# Antenna_and_LoRa.net
KiCad netlist of a schematic drawn in Altium Designer
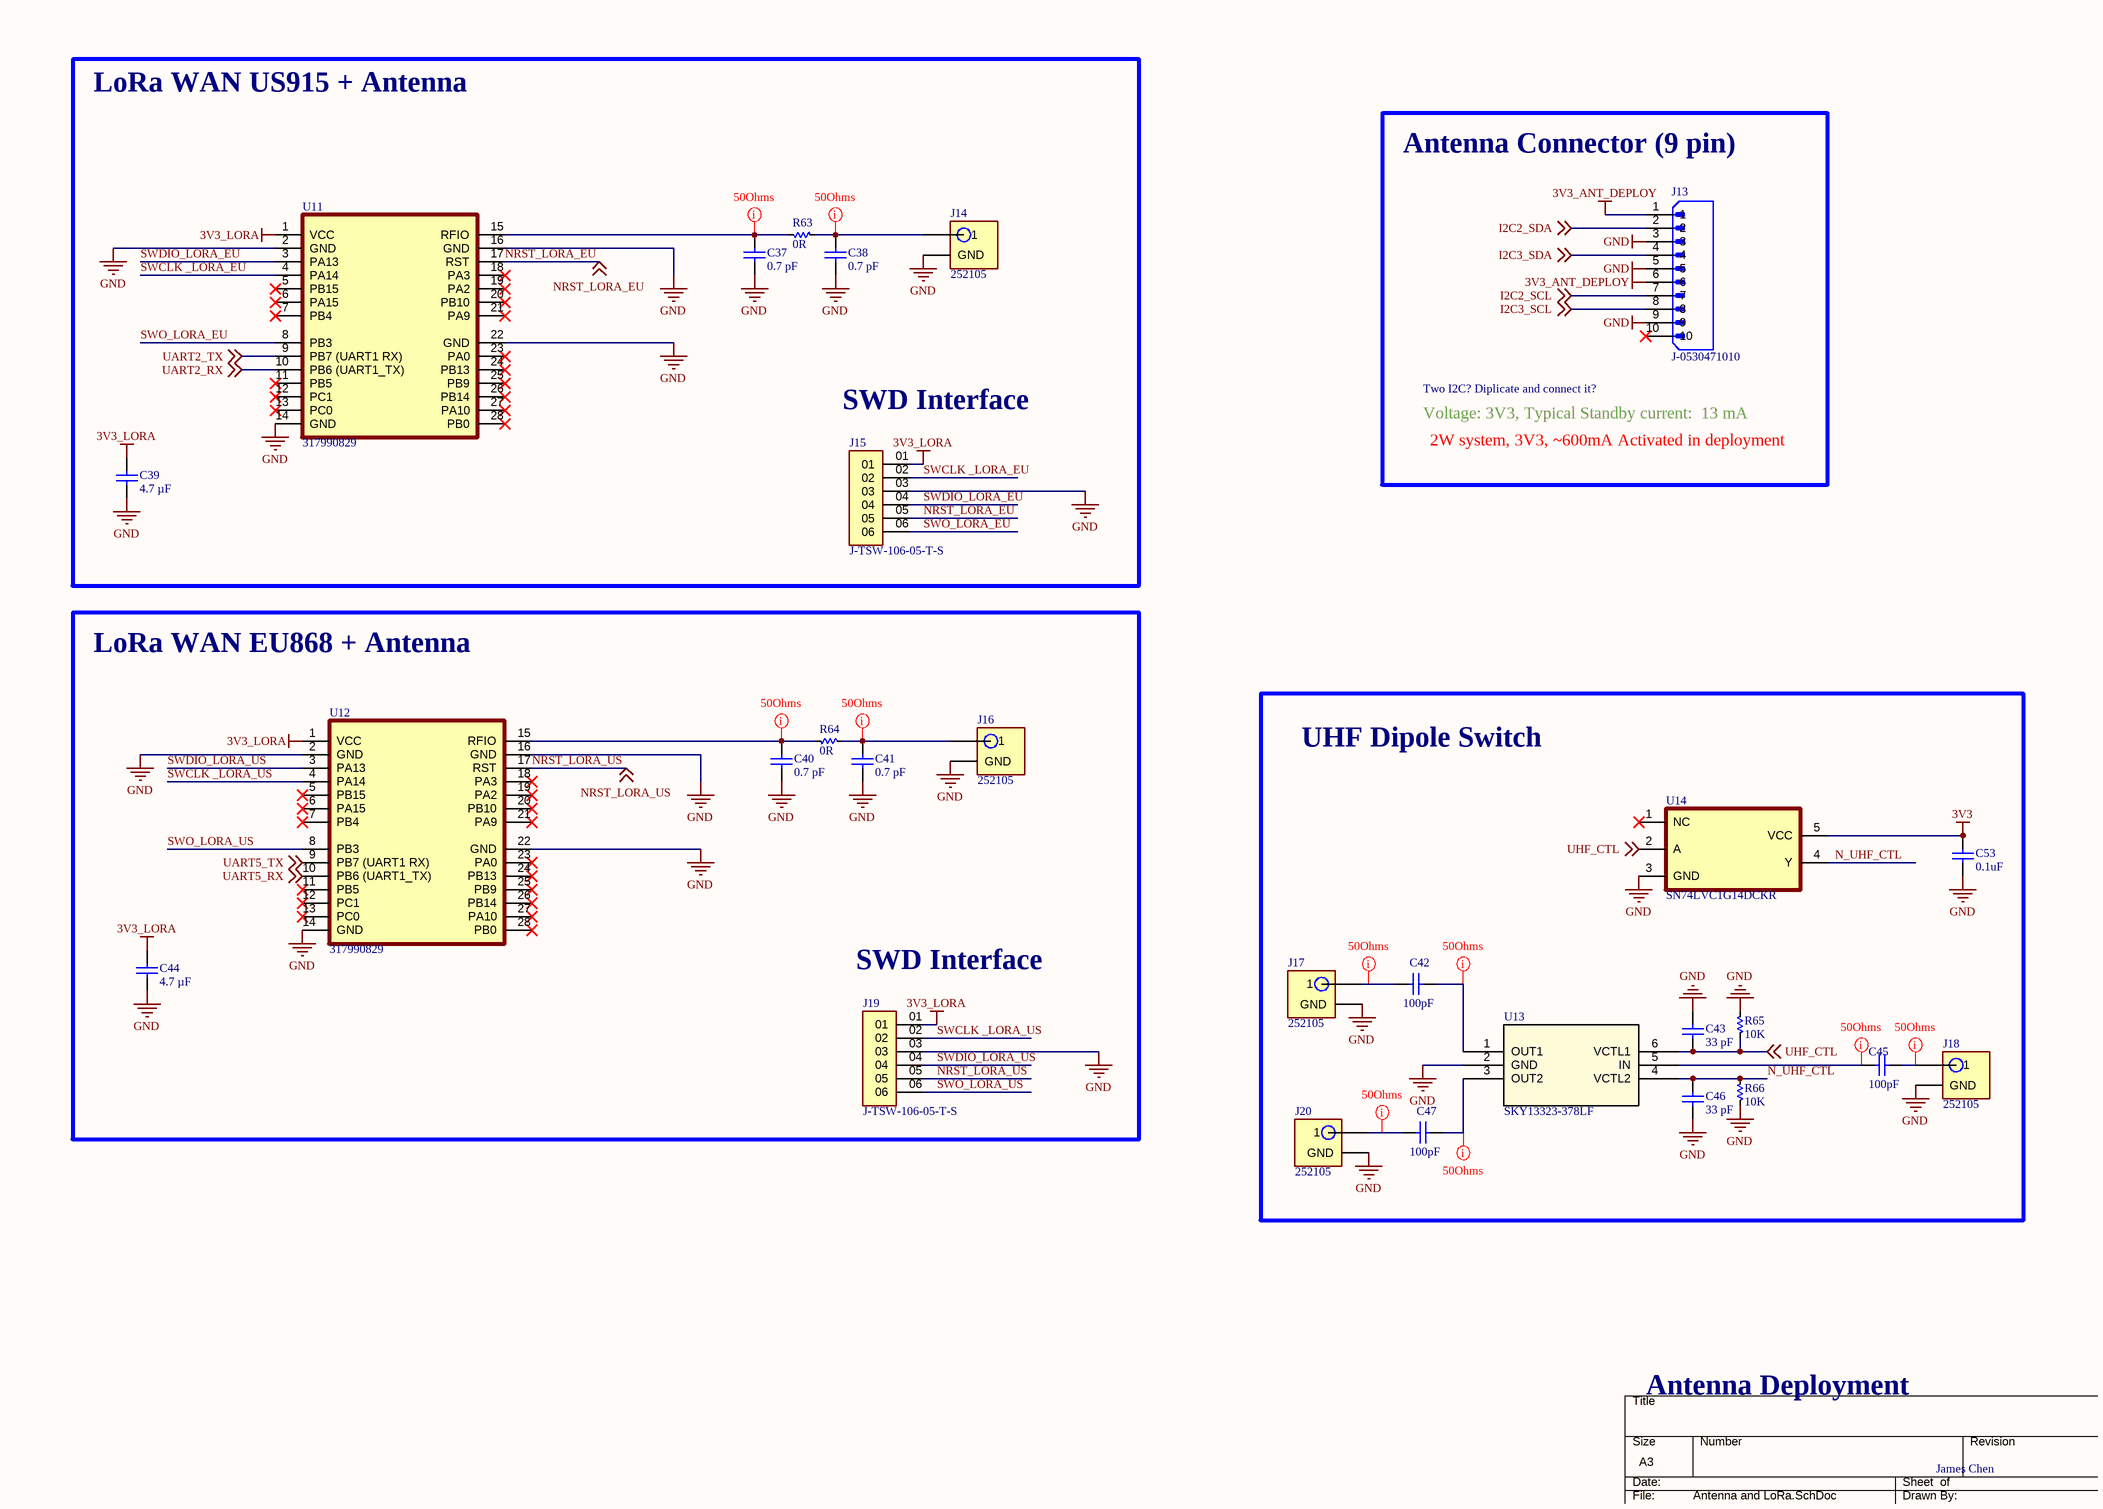
[diagram p0: Antenna and LoRa.SchDoc]

(export (version "E")
  (design (tool "Eeschema 10.0.6"))
  (components
    (comp (ref "C37")
      (value "0.7 pF")
      (footprint "0603")
      (description "CAP CER 0.7PF 50V NP0 0603")
      (fields
        (field (name "DISTRIBUTOR PART #") "399-CBR06C708B5GACCT-ND")
        (field (name "MANUFACTURER") "KEMET")
      )
      (libsource (lib "UHF Radio rev1.0") (part "CC-710-K-50V-X7R-0603"))
    )
    (comp (ref "C38")
      (value "0.7 pF")
      (footprint "0603")
      (description "CAP CER 0.7PF 50V NP0 0603")
      (fields
        (field (name "DISTRIBUTOR PART #") "399-CBR06C708B5GACCT-ND")
        (field (name "MANUFACTURER") "KEMET")
      )
      (libsource (lib "UHF Radio rev1.0") (part "CC-710-K-50V-X7R-0603"))
    )
    (comp (ref "C39")
      (value "4.7 µF")
      (footprint "0603")
      (description "CAP CER 4.7UF 16V X7R 0603")
      (fields
        (field (name "DISTRIBUTOR PART #") "490-GRM188Z71C475KE21JCT-ND")
        (field (name "MANUFACTURER") "Murata Electronics")
      )
      (libsource (lib "RS2D") (part "CC-475-K-16V-X7R-0603"))
    )
    (comp (ref "C40")
      (value "0.7 pF")
      (footprint "0603")
      (description "CAP CER 0.7PF 50V NP0 0603")
      (fields
        (field (name "DISTRIBUTOR PART #") "399-CBR06C708B5GACCT-ND")
        (field (name "MANUFACTURER") "KEMET")
      )
      (libsource (lib "UHF Radio rev1.0") (part "CC-710-K-50V-X7R-0603"))
    )
    (comp (ref "C41")
      (value "0.7 pF")
      (footprint "0603")
      (description "CAP CER 0.7PF 50V NP0 0603")
      (fields
        (field (name "DISTRIBUTOR PART #") "399-CBR06C708B5GACCT-ND")
        (field (name "MANUFACTURER") "KEMET")
      )
      (libsource (lib "UHF Radio rev1.0") (part "CC-710-K-50V-X7R-0603"))
    )
    (comp (ref "C42")
      (value "100pF")
      (footprint "0603")
      (description "CAP CER 100PF 50V X7R 0603")
      (fields (field (name "DISTRIBUTOR PART #") "311-3601-1-ND") (field (name "MANUFACTURER") "YAGEO"))
      (libsource (lib "RS2D") (part "CC-108-K-50V-X7R-0603"))
    )
    (comp (ref "C43")
      (value "33 pF")
      (footprint "0603")
      (description "CAP CER 33PF 50V X7R 0603")
      (fields
        (field (name "DISTRIBUTOR PART #") "399-C0603C330K5RAC7867CT-ND")
        (field (name "MANUFACTURER") "KEMET")
      )
      (libsource (lib "OBC Development Board") (part "CC-339-K-50V-X7R-0603"))
    )
    (comp (ref "C44")
      (value "4.7 µF")
      (footprint "0603")
      (description "CAP CER 4.7UF 16V X7R 0603")
      (fields
        (field (name "DISTRIBUTOR PART #") "490-GRM188Z71C475KE21JCT-ND")
        (field (name "MANUFACTURER") "Murata Electronics")
      )
      (libsource (lib "RS2D") (part "CC-475-K-16V-X7R-0603"))
    )
    (comp (ref "C45")
      (value "100pF")
      (footprint "0603")
      (description "CAP CER 100PF 50V X7R 0603")
      (fields (field (name "DISTRIBUTOR PART #") "311-3601-1-ND") (field (name "MANUFACTURER") "YAGEO"))
      (libsource (lib "RS2D") (part "CC-108-K-50V-X7R-0603"))
    )
    (comp (ref "C46")
      (value "33 pF")
      (footprint "0603")
      (description "CAP CER 33PF 50V X7R 0603")
      (fields
        (field (name "DISTRIBUTOR PART #") "399-C0603C330K5RAC7867CT-ND")
        (field (name "MANUFACTURER") "KEMET")
      )
      (libsource (lib "OBC Development Board") (part "CC-339-K-50V-X7R-0603"))
    )
    (comp (ref "C47")
      (value "100pF")
      (footprint "0603")
      (description "CAP CER 100PF 50V X7R 0603")
      (fields (field (name "DISTRIBUTOR PART #") "311-3601-1-ND") (field (name "MANUFACTURER") "YAGEO"))
      (libsource (lib "RS2D") (part "CC-108-K-50V-X7R-0603"))
    )
    (comp (ref "C53")
      (value "0.1uF")
      (footprint "0603")
      (description "0.1 µF ±10% 25V Ceramic Capacitor X7R 0603 (1608 Metric)")
      (fields
        (field (name "DISTRIBUTOR PART #") "1276-1006-1-ND")
        (field (name "MANUFACTURER") "Samsung Electro-Mechanics")
      )
      (libsource (lib "OBC Development Board") (part "CC-104-K-25V-X7R-0603"))
    )
    (comp (ref "J13")
      (value "J-0530471010")
      (footprint "J-0530471010")
      (description "CONN HEADER VERT 10POS 1.25MM")
      (fields (field (name "MANUFACTURER") "Molex") (field (name "MANUFACTURER PART #") "0530471010"))
      (libsource (lib "OBC Development Board") (part "J-0530471010"))
    )
    (comp (ref "J14")
      (value "252105")
      (footprint "J-252105")
      (description "CONN MCX RCPT STR 50 OHM PCB")
      (fields (field (name "MANUFACTURER") "Amphenol RF") (field (name "DISTRIBUTOR PART #") "ACX1262-ND"))
      (libsource (lib "OBC Development Board") (part "J-252105"))
    )
    (comp (ref "J15")
      (value "J-TSW-106-05-T-S")
      (footprint "J-TSW-106-05-T-S")
      (description "CONN HEADER VERT 6POS 2.54MM")
      (fields
        (field (name "DISTRBUTOR PART #") "SAM12323-ND")
        (field (name "MANUFACTURER PART #") "TSW-106-05-T-S")
      )
      (libsource (lib "OBC Development Board") (part "J-TSW-106-05-T-S"))
    )
    (comp (ref "J16")
      (value "252105")
      (footprint "J-252105")
      (description "CONN MCX RCPT STR 50 OHM PCB")
      (fields (field (name "MANUFACTURER") "Amphenol RF") (field (name "DISTRIBUTOR PART #") "ACX1262-ND"))
      (libsource (lib "OBC Development Board") (part "J-252105"))
    )
    (comp (ref "J17")
      (value "252105")
      (footprint "J-252105")
      (description "CONN MCX RCPT STR 50 OHM PCB")
      (fields (field (name "MANUFACTURER") "Amphenol RF") (field (name "DISTRIBUTOR PART #") "ACX1262-ND"))
      (libsource (lib "") (part "J-252105_1"))
    )
    (comp (ref "J18")
      (value "252105")
      (footprint "J-252105")
      (description "CONN MCX RCPT STR 50 OHM PCB")
      (fields (field (name "MANUFACTURER") "Amphenol RF") (field (name "DISTRIBUTOR PART #") "ACX1262-ND"))
      (libsource (lib "OBC Development Board") (part "J-252105"))
    )
    (comp (ref "J19")
      (value "J-TSW-106-05-T-S")
      (footprint "J-TSW-106-05-T-S")
      (description "CONN HEADER VERT 6POS 2.54MM")
      (fields
        (field (name "DISTRBUTOR PART #") "SAM12323-ND")
        (field (name "MANUFACTURER PART #") "TSW-106-05-T-S")
      )
      (libsource (lib "OBC Development Board") (part "J-TSW-106-05-T-S"))
    )
    (comp (ref "J20")
      (value "252105")
      (footprint "J-252105")
      (description "CONN MCX RCPT STR 50 OHM PCB")
      (fields (field (name "MANUFACTURER") "Amphenol RF") (field (name "DISTRIBUTOR PART #") "ACX1262-ND"))
      (libsource (lib "") (part "J-252105_1"))
    )
    (comp (ref "R63")
      (value "0R")
      (footprint "0603")
      (description "0 Ohms Jumper 0.1W, 1/10W Chip Resistor 0603 (1608 Metric) Automotive AEC-Q200 Thick Film")
      (fields
        (field (name "DISTRIBUTOR PART #") "RMCF0603ZT0R00CT-ND")
        (field (name "MANUFACTURER") "Stackpole Electronics Inc")
      )
      (libsource (lib "OBC Development Board") (part "RT-0R00-F-1/10W-0603"))
    )
    (comp (ref "R64")
      (value "0R")
      (footprint "0603")
      (description "0 Ohms Jumper 0.1W, 1/10W Chip Resistor 0603 (1608 Metric) Automotive AEC-Q200 Thick Film")
      (fields
        (field (name "DISTRIBUTOR PART #") "RMCF0603ZT0R00CT-ND")
        (field (name "MANUFACTURER") "Stackpole Electronics Inc")
      )
      (libsource (lib "OBC Development Board") (part "RT-0R00-F-1/10W-0603"))
    )
    (comp (ref "R65")
      (value "10K")
      (footprint "0603")
      (description "10 kOhms ±0.1% 0.063W, 1/16W Chip Resistor 0603 (1608 Metric) - Thin Film")
      (fields
        (field (name "DISTRIBUTOR PART #") "A119886CT-ND")
        (field (name "MANUFACTURER") "TE Connectivity Passive Product")
      )
      (libsource (lib "OBC Development Board") (part "RT-10K0-F-1/16W-0603"))
    )
    (comp (ref "R66")
      (value "10K")
      (footprint "0603")
      (description "10 kOhms ±0.1% 0.063W, 1/16W Chip Resistor 0603 (1608 Metric) - Thin Film")
      (fields
        (field (name "DISTRIBUTOR PART #") "A119886CT-ND")
        (field (name "MANUFACTURER") "TE Connectivity Passive Product")
      )
      (libsource (lib "OBC Development Board") (part "RT-10K0-F-1/16W-0603"))
    )
    (comp (ref "U11")
      (value "317990829")
      (footprint "U-LORA-E5")
      (description "LORA-E5 WIRELESS MODULE (TAPE RE")
      (fields
        (field (name "MANUFACTURER") "Seeed Technology Co., Ltd")
        (field (name "DISTRIBUTOR PART #") "1597-317990829CT-ND")
      )
      (libsource (lib "OBC Development Board") (part "U-LORA-E5"))
    )
    (comp (ref "U12")
      (value "317990829")
      (footprint "U-LORA-E5")
      (description "LORA-E5 WIRELESS MODULE (TAPE RE")
      (fields
        (field (name "MANUFACTURER") "Seeed Technology Co., Ltd")
        (field (name "DISTRIBUTOR PART #") "1597-317990829CT-ND")
      )
      (libsource (lib "OBC Development Board") (part "U-LORA-E5"))
    )
    (comp (ref "U13")
      (value "SKY13323-378LF")
      (footprint "U-SKY13323-378LF")
      (description "IC RF SWITCH SPDT 3GHZ 6MLPD")
      (fields
        (field (name "MANUFACTURER") "Skyworks Solutions Inc.")
        (field (name "DISTRBUTOR PART #") "683-1334-1-ND")
      )
      (libsource (lib "OBC Development Board") (part "U-SKY13323-378LF"))
    )
    (comp (ref "U14")
      (value "SN74LVC1G14DCKR")
      (footprint "U-SN74LVC1G14DCKR")
      (description "IC INVERT SCHMITT 1CH 1IN SC70")
      (fields (field (name "DISTRIBUTOR PART NUMBER") "296-11608-1-ND"))
      (libsource (lib "OBC Development Board") (part "U-SN74LVC1G14DCKR"))
    )
  )
  (nets
    (net (code "1") (name "/N_UHF_CTL") (class "Default")
      (node (ref "C46") (pin "2") (pinfunction "2_2") (pintype "passive"))
      (node (ref "R66") (pin "2") (pintype "passive"))
      (node (ref "U13") (pin "4") (pinfunction "VCTL2_4") (pintype "passive"))
      (node (ref "U14") (pin "4") (pinfunction "Y_4") (pintype "passive"))
    )
    (net (code "2") (name "/SWCLK _LORA_EU") (class "Default")
      (node (ref "J15") (pin "02") (pinfunction "02_02") (pintype "passive"))
      (node (ref "U11") (pin "4") (pinfunction "PA14_4") (pintype "passive"))
    )
    (net (code "3") (name "/SWCLK _LORA_US") (class "Default")
      (node (ref "J19") (pin "02") (pinfunction "02_02") (pintype "passive"))
      (node (ref "U12") (pin "4") (pinfunction "PA14_4") (pintype "passive"))
    )
    (net (code "4") (name "/SWDIO_LORA_EU") (class "Default")
      (node (ref "J15") (pin "04") (pinfunction "04_04") (pintype "passive"))
      (node (ref "U11") (pin "3") (pinfunction "PA13_3") (pintype "passive"))
    )
    (net (code "5") (name "/SWDIO_LORA_US") (class "Default")
      (node (ref "J19") (pin "04") (pinfunction "04_04") (pintype "passive"))
      (node (ref "U12") (pin "3") (pinfunction "PA13_3") (pintype "passive"))
    )
    (net (code "6") (name "/SWO_LORA_EU") (class "Default")
      (node (ref "J15") (pin "06") (pinfunction "06_06") (pintype "passive"))
      (node (ref "U11") (pin "8") (pinfunction "PB3_8") (pintype "passive"))
    )
    (net (code "7") (name "/SWO_LORA_US") (class "Default")
      (node (ref "J19") (pin "06") (pinfunction "06_06") (pintype "passive"))
      (node (ref "U12") (pin "8") (pinfunction "PB3_8") (pintype "passive"))
    )
    (net (code "8") (name "3V3") (class "Default")
      (node (ref "C53") (pin "2") (pinfunction "2_2") (pintype "passive"))
      (node (ref "U14") (pin "5") (pinfunction "VCC_5") (pintype "passive"))
    )
    (net (code "9") (name "3V3_ANT_DEPLOY") (class "Default")
      (node (ref "J13") (pin "1") (pinfunction "1_1") (pintype "passive"))
      (node (ref "J13") (pin "6") (pinfunction "6_6") (pintype "passive"))
    )
    (net (code "10") (name "3V3_LORA") (class "Default")
      (node (ref "C39") (pin "2") (pinfunction "2_2") (pintype "passive"))
      (node (ref "C44") (pin "2") (pinfunction "2_2") (pintype "passive"))
      (node (ref "J15") (pin "01") (pinfunction "01_01") (pintype "passive"))
      (node (ref "J19") (pin "01") (pinfunction "01_01") (pintype "passive"))
      (node (ref "U11") (pin "1") (pinfunction "VCC_1") (pintype "passive"))
      (node (ref "U12") (pin "1") (pinfunction "VCC_1") (pintype "passive"))
    )
    (net (code "11") (name "GND") (class "Default")
      (node (ref "C37") (pin "1") (pinfunction "1_1") (pintype "passive"))
      (node (ref "C38") (pin "1") (pinfunction "1_1") (pintype "passive"))
      (node (ref "C39") (pin "1") (pinfunction "1_1") (pintype "passive"))
      (node (ref "C40") (pin "1") (pinfunction "1_1") (pintype "passive"))
      (node (ref "C41") (pin "1") (pinfunction "1_1") (pintype "passive"))
      (node (ref "C43") (pin "2") (pinfunction "2_2") (pintype "passive"))
      (node (ref "C44") (pin "1") (pinfunction "1_1") (pintype "passive"))
      (node (ref "C46") (pin "1") (pinfunction "1_1") (pintype "passive"))
      (node (ref "C53") (pin "1") (pinfunction "1_1") (pintype "passive"))
      (node (ref "J13") (pin "3") (pinfunction "3_3") (pintype "passive"))
      (node (ref "J13") (pin "5") (pinfunction "5_5") (pintype "passive"))
      (node (ref "J13") (pin "9") (pinfunction "9_9") (pintype "passive"))
      (node (ref "J14") (pin "0") (pinfunction "GND_0") (pintype "passive"))
      (node (ref "J15") (pin "03") (pinfunction "03_03") (pintype "passive"))
      (node (ref "J16") (pin "0") (pinfunction "GND_0") (pintype "passive"))
      (node (ref "J17") (pin "0") (pinfunction "GND_0") (pintype "passive"))
      (node (ref "J18") (pin "0") (pinfunction "GND_0") (pintype "passive"))
      (node (ref "J19") (pin "03") (pinfunction "03_03") (pintype "passive"))
      (node (ref "J20") (pin "0") (pinfunction "GND_0") (pintype "passive"))
      (node (ref "R65") (pin "2") (pintype "passive"))
      (node (ref "R66") (pin "1") (pintype "passive"))
      (node (ref "U11") (pin "14") (pinfunction "GND_14") (pintype "passive"))
      (node (ref "U11") (pin "16") (pinfunction "GND_16") (pintype "passive"))
      (node (ref "U11") (pin "2") (pinfunction "GND_2") (pintype "passive"))
      (node (ref "U11") (pin "22") (pinfunction "GND_22") (pintype "passive"))
      (node (ref "U12") (pin "14") (pinfunction "GND_14") (pintype "passive"))
      (node (ref "U12") (pin "16") (pinfunction "GND_16") (pintype "passive"))
      (node (ref "U12") (pin "2") (pinfunction "GND_2") (pintype "passive"))
      (node (ref "U12") (pin "22") (pinfunction "GND_22") (pintype "passive"))
      (node (ref "U13") (pin "2") (pinfunction "GND_2") (pintype "passive"))
      (node (ref "U14") (pin "3") (pinfunction "GND_3") (pintype "passive"))
    )
    (net (code "12") (name "I2C2_SCL") (class "Default")
      (node (ref "J13") (pin "7") (pinfunction "7_7") (pintype "passive"))
    )
    (net (code "13") (name "I2C2_SDA") (class "Default")
      (node (ref "J13") (pin "2") (pinfunction "2_2") (pintype "passive"))
    )
    (net (code "14") (name "I2C3_SCL") (class "Default")
      (node (ref "J13") (pin "8") (pinfunction "8_8") (pintype "passive"))
    )
    (net (code "15") (name "I2C3_SDA") (class "Default")
      (node (ref "J13") (pin "4") (pinfunction "4_4") (pintype "passive"))
    )
    (net (code "16") (name "NRST_LORA_EU") (class "Default")
      (node (ref "J15") (pin "05") (pinfunction "05_05") (pintype "passive"))
      (node (ref "U11") (pin "17") (pinfunction "RST_17") (pintype "passive"))
    )
    (net (code "17") (name "NRST_LORA_US") (class "Default")
      (node (ref "J19") (pin "05") (pinfunction "05_05") (pintype "passive"))
      (node (ref "U12") (pin "17") (pinfunction "RST_17") (pintype "passive"))
    )
    (net (code "18") (name "Net-(C38-Pad2)") (class "Default")
      (node (ref "C38") (pin "2") (pinfunction "2_2") (pintype "passive"))
      (node (ref "J14") (pin "1") (pinfunction "1_1") (pintype "passive"))
      (node (ref "R63") (pin "2") (pintype "passive"))
    )
    (net (code "19") (name "Net-(C41-Pad2)") (class "Default")
      (node (ref "C41") (pin "2") (pinfunction "2_2") (pintype "passive"))
      (node (ref "J16") (pin "1") (pinfunction "1_1") (pintype "passive"))
      (node (ref "R64") (pin "2") (pintype "passive"))
    )
    (net (code "20") (name "Net-(C42-Pad1)") (class "Default")
      (node (ref "C42") (pin "1") (pinfunction "1_1") (pintype "passive"))
      (node (ref "J17") (pin "1") (pinfunction "1_1") (pintype "passive"))
    )
    (net (code "21") (name "Net-(C45-Pad2)") (class "Default")
      (node (ref "C45") (pin "2") (pinfunction "2_2") (pintype "passive"))
      (node (ref "J18") (pin "1") (pinfunction "1_1") (pintype "passive"))
    )
    (net (code "22") (name "Net-(C47-Pad1)") (class "Default")
      (node (ref "C47") (pin "1") (pinfunction "1_1") (pintype "passive"))
      (node (ref "J20") (pin "1") (pinfunction "1_1") (pintype "passive"))
    )
    (net (code "23") (name "Net-(U11-RFIO)") (class "Default")
      (node (ref "C37") (pin "2") (pinfunction "2_2") (pintype "passive"))
      (node (ref "R63") (pin "1") (pintype "passive"))
      (node (ref "U11") (pin "15") (pinfunction "RFIO_15") (pintype "passive"))
    )
    (net (code "24") (name "Net-(U12-RFIO)") (class "Default")
      (node (ref "C40") (pin "2") (pinfunction "2_2") (pintype "passive"))
      (node (ref "R64") (pin "1") (pintype "passive"))
      (node (ref "U12") (pin "15") (pinfunction "RFIO_15") (pintype "passive"))
    )
    (net (code "25") (name "Net-(U13-IN)") (class "Default")
      (node (ref "C45") (pin "1") (pinfunction "1_1") (pintype "passive"))
      (node (ref "U13") (pin "5") (pinfunction "IN_5") (pintype "passive"))
    )
    (net (code "26") (name "Net-(U13-OUT1)") (class "Default")
      (node (ref "C42") (pin "2") (pinfunction "2_2") (pintype "passive"))
      (node (ref "U13") (pin "1") (pinfunction "OUT1_1") (pintype "passive"))
    )
    (net (code "27") (name "Net-(U13-OUT2)") (class "Default")
      (node (ref "C47") (pin "2") (pinfunction "2_2") (pintype "passive"))
      (node (ref "U13") (pin "3") (pinfunction "OUT2_3") (pintype "passive"))
    )
    (net (code "28") (name "UART2_RX") (class "Default")
      (node (ref "U11") (pin "10") (pinfunction "PB6_(UART1_TX)_10") (pintype "passive"))
    )
    (net (code "29") (name "UART2_TX") (class "Default")
      (node (ref "U11") (pin "9") (pinfunction "PB7_(UART1_RX)_9") (pintype "passive"))
    )
    (net (code "30") (name "UART5_RX") (class "Default")
      (node (ref "U12") (pin "10") (pinfunction "PB6_(UART1_TX)_10") (pintype "passive"))
    )
    (net (code "31") (name "UART5_TX") (class "Default")
      (node (ref "U12") (pin "9") (pinfunction "PB7_(UART1_RX)_9") (pintype "passive"))
    )
    (net (code "32") (name "UHF_CTL") (class "Default")
      (node (ref "C43") (pin "1") (pinfunction "1_1") (pintype "passive"))
      (node (ref "R65") (pin "1") (pintype "passive"))
      (node (ref "U13") (pin "6") (pinfunction "VCTL1_6") (pintype "passive"))
      (node (ref "U14") (pin "2") (pinfunction "A_2") (pintype "passive"))
    )
    (net (code "33") (name "unconnected-(J13-Pad10)") (class "Default")
      (node (ref "J13") (pin "10") (pinfunction "10_10") (pintype "passive+no_connect"))
    )
    (net (code "34") (name "unconnected-(U11-PA0-Pad23)") (class "Default")
      (node (ref "U11") (pin "23") (pinfunction "PA0_23") (pintype "passive+no_connect"))
    )
    (net (code "35") (name "unconnected-(U11-PA2-Pad19)") (class "Default")
      (node (ref "U11") (pin "19") (pinfunction "PA2_19") (pintype "passive+no_connect"))
    )
    (net (code "36") (name "unconnected-(U11-PA3-Pad18)") (class "Default")
      (node (ref "U11") (pin "18") (pinfunction "PA3_18") (pintype "passive+no_connect"))
    )
    (net (code "37") (name "unconnected-(U11-PA9-Pad21)") (class "Default")
      (node (ref "U11") (pin "21") (pinfunction "PA9_21") (pintype "passive+no_connect"))
    )
    (net (code "38") (name "unconnected-(U11-PA10-Pad27)") (class "Default")
      (node (ref "U11") (pin "27") (pinfunction "PA10_27") (pintype "passive+no_connect"))
    )
    (net (code "39") (name "unconnected-(U11-PA15-Pad6)") (class "Default")
      (node (ref "U11") (pin "6") (pinfunction "PA15_6") (pintype "passive+no_connect"))
    )
    (net (code "40") (name "unconnected-(U11-PB0-Pad28)") (class "Default")
      (node (ref "U11") (pin "28") (pinfunction "PB0_28") (pintype "passive+no_connect"))
    )
    (net (code "41") (name "unconnected-(U11-PB4-Pad7)") (class "Default")
      (node (ref "U11") (pin "7") (pinfunction "PB4_7") (pintype "passive+no_connect"))
    )
    (net (code "42") (name "unconnected-(U11-PB5-Pad11)") (class "Default")
      (node (ref "U11") (pin "11") (pinfunction "PB5_11") (pintype "passive+no_connect"))
    )
    (net (code "43") (name "unconnected-(U11-PB9-Pad25)") (class "Default")
      (node (ref "U11") (pin "25") (pinfunction "PB9_25") (pintype "passive+no_connect"))
    )
    (net (code "44") (name "unconnected-(U11-PB10-Pad20)") (class "Default")
      (node (ref "U11") (pin "20") (pinfunction "PB10_20") (pintype "passive+no_connect"))
    )
    (net (code "45") (name "unconnected-(U11-PB13-Pad24)") (class "Default")
      (node (ref "U11") (pin "24") (pinfunction "PB13_24") (pintype "passive+no_connect"))
    )
    (net (code "46") (name "unconnected-(U11-PB14-Pad26)") (class "Default")
      (node (ref "U11") (pin "26") (pinfunction "PB14_26") (pintype "passive+no_connect"))
    )
    (net (code "47") (name "unconnected-(U11-PB15-Pad5)") (class "Default")
      (node (ref "U11") (pin "5") (pinfunction "PB15_5") (pintype "passive+no_connect"))
    )
    (net (code "48") (name "unconnected-(U11-PC0-Pad13)") (class "Default")
      (node (ref "U11") (pin "13") (pinfunction "PC0_13") (pintype "passive+no_connect"))
    )
    (net (code "49") (name "unconnected-(U11-PC1-Pad12)") (class "Default")
      (node (ref "U11") (pin "12") (pinfunction "PC1_12") (pintype "passive+no_connect"))
    )
    (net (code "50") (name "unconnected-(U12-PA0-Pad23)") (class "Default")
      (node (ref "U12") (pin "23") (pinfunction "PA0_23") (pintype "passive+no_connect"))
    )
    (net (code "51") (name "unconnected-(U12-PA2-Pad19)") (class "Default")
      (node (ref "U12") (pin "19") (pinfunction "PA2_19") (pintype "passive+no_connect"))
    )
    (net (code "52") (name "unconnected-(U12-PA3-Pad18)") (class "Default")
      (node (ref "U12") (pin "18") (pinfunction "PA3_18") (pintype "passive+no_connect"))
    )
    (net (code "53") (name "unconnected-(U12-PA9-Pad21)") (class "Default")
      (node (ref "U12") (pin "21") (pinfunction "PA9_21") (pintype "passive+no_connect"))
    )
    (net (code "54") (name "unconnected-(U12-PA10-Pad27)") (class "Default")
      (node (ref "U12") (pin "27") (pinfunction "PA10_27") (pintype "passive+no_connect"))
    )
    (net (code "55") (name "unconnected-(U12-PA15-Pad6)") (class "Default")
      (node (ref "U12") (pin "6") (pinfunction "PA15_6") (pintype "passive+no_connect"))
    )
    (net (code "56") (name "unconnected-(U12-PB0-Pad28)") (class "Default")
      (node (ref "U12") (pin "28") (pinfunction "PB0_28") (pintype "passive+no_connect"))
    )
    (net (code "57") (name "unconnected-(U12-PB4-Pad7)") (class "Default")
      (node (ref "U12") (pin "7") (pinfunction "PB4_7") (pintype "passive+no_connect"))
    )
    (net (code "58") (name "unconnected-(U12-PB5-Pad11)") (class "Default")
      (node (ref "U12") (pin "11") (pinfunction "PB5_11") (pintype "passive+no_connect"))
    )
    (net (code "59") (name "unconnected-(U12-PB9-Pad25)") (class "Default")
      (node (ref "U12") (pin "25") (pinfunction "PB9_25") (pintype "passive+no_connect"))
    )
    (net (code "60") (name "unconnected-(U12-PB10-Pad20)") (class "Default")
      (node (ref "U12") (pin "20") (pinfunction "PB10_20") (pintype "passive+no_connect"))
    )
    (net (code "61") (name "unconnected-(U12-PB13-Pad24)") (class "Default")
      (node (ref "U12") (pin "24") (pinfunction "PB13_24") (pintype "passive+no_connect"))
    )
    (net (code "62") (name "unconnected-(U12-PB14-Pad26)") (class "Default")
      (node (ref "U12") (pin "26") (pinfunction "PB14_26") (pintype "passive+no_connect"))
    )
    (net (code "63") (name "unconnected-(U12-PB15-Pad5)") (class "Default")
      (node (ref "U12") (pin "5") (pinfunction "PB15_5") (pintype "passive+no_connect"))
    )
    (net (code "64") (name "unconnected-(U12-PC0-Pad13)") (class "Default")
      (node (ref "U12") (pin "13") (pinfunction "PC0_13") (pintype "passive+no_connect"))
    )
    (net (code "65") (name "unconnected-(U12-PC1-Pad12)") (class "Default")
      (node (ref "U12") (pin "12") (pinfunction "PC1_12") (pintype "passive+no_connect"))
    )
    (net (code "66") (name "unconnected-(U14-NC-Pad1)") (class "Default")
      (node (ref "U14") (pin "1") (pinfunction "NC_1") (pintype "passive+no_connect"))
    )
  )
)
